# Auxillary_Supply_UCC28740.net
KiCad netlist of a schematic drawn in Altium Designer
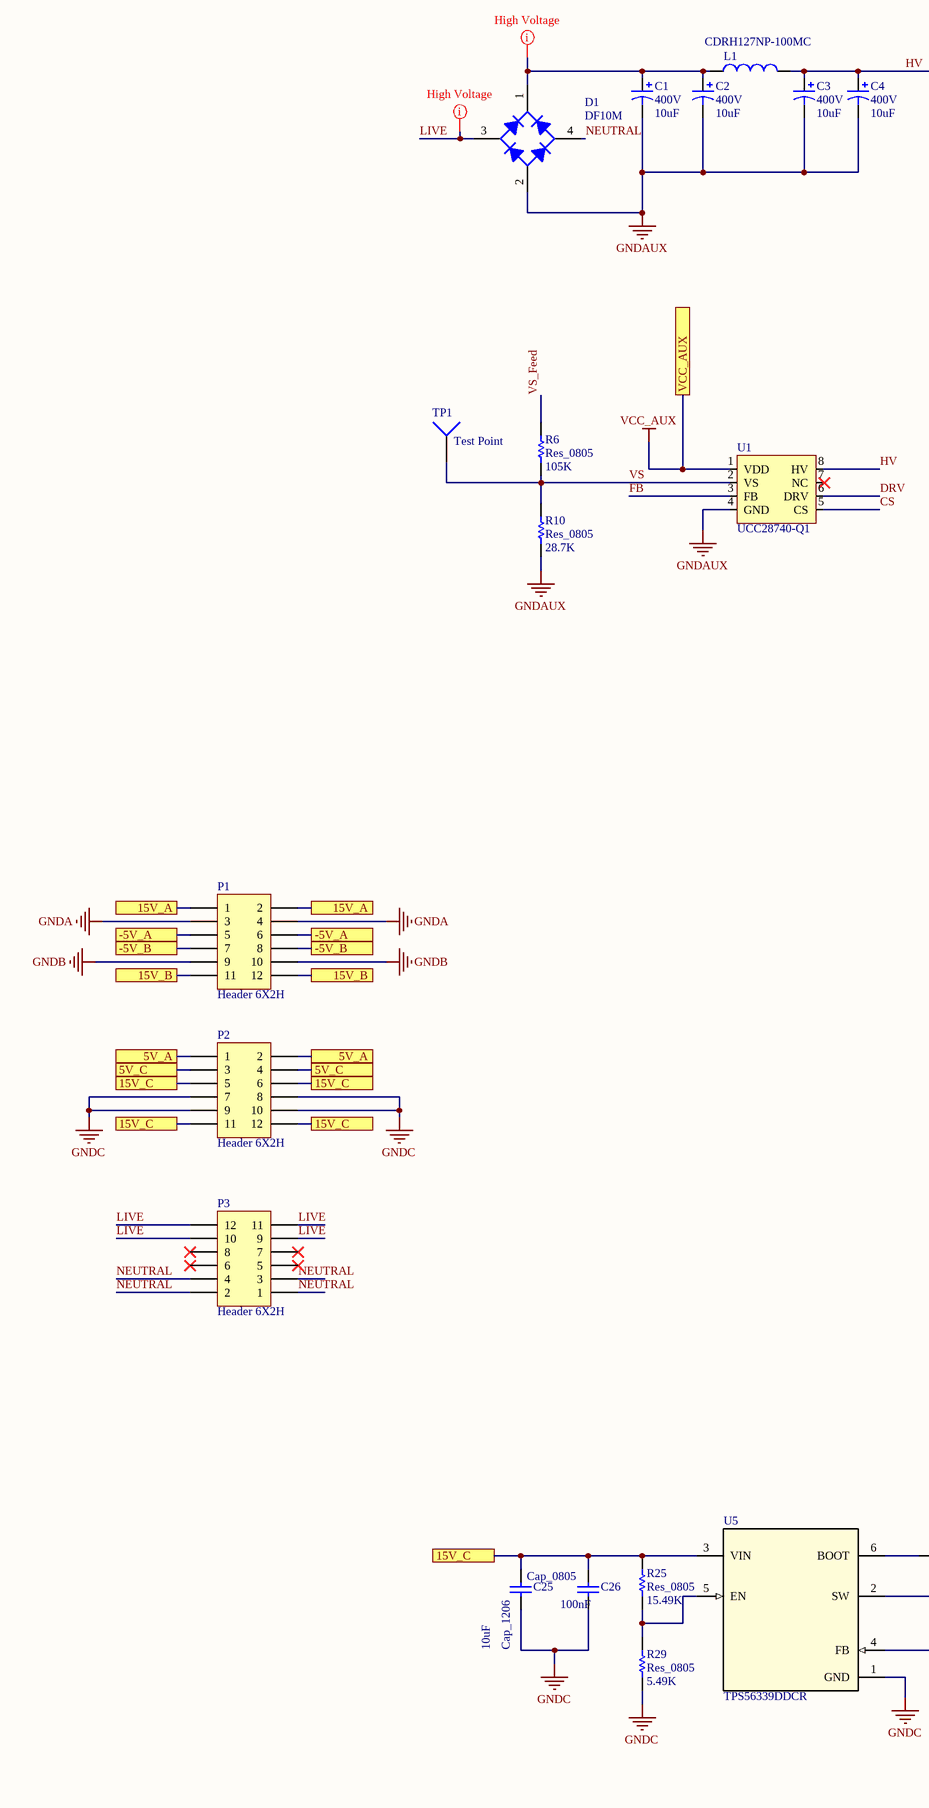
[diagram p0: Auxillary_Supply_UCC28740.SchDoc, left]
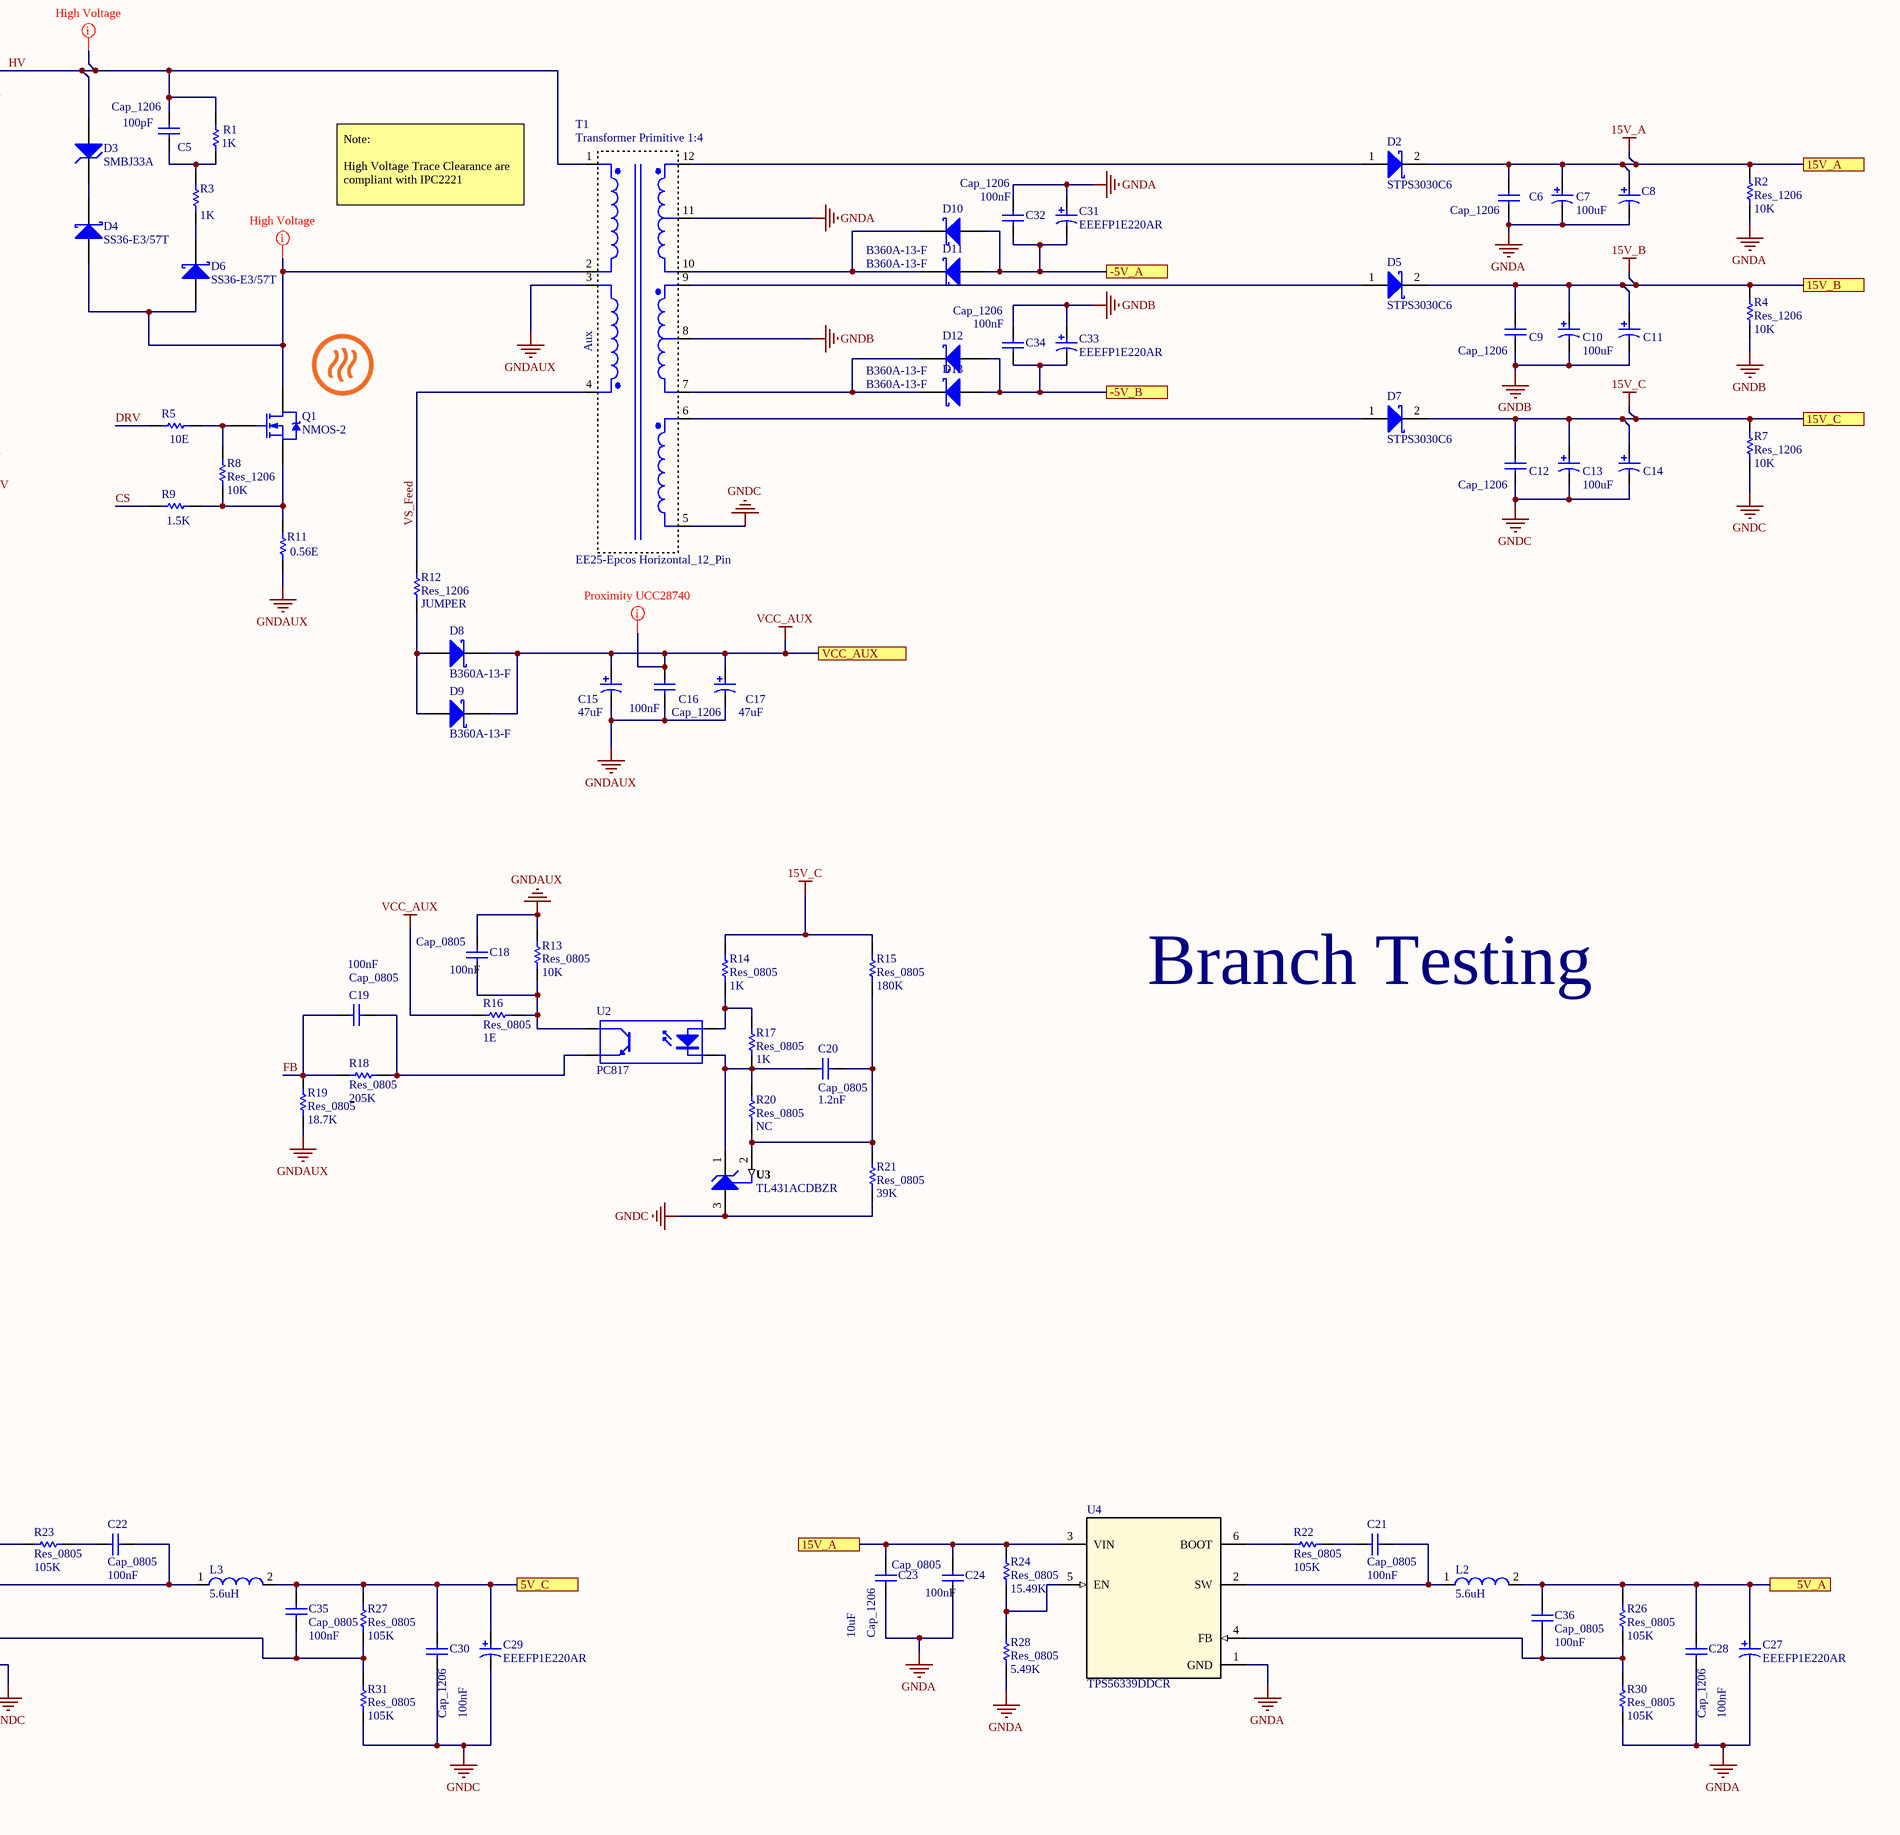
[diagram p1: Auxillary_Supply_UCC28740.SchDoc, right]

(export (version "E")
  (design (tool "Eeschema 10.0.6"))
  (components
    (comp (ref "C1")
      (value "400V")
      (footprint "10uF_400V")
      (description "Polarized Capacitor (Radial)")
      (fields (field (name "ALTIUM_VALUE") "10uF") (field (name "PUBLISHER") "Altium Limited"))
      (libsource (lib "Miscellaneous Devices") (part "Cap Pol1"))
    )
    (comp (ref "C2")
      (value "400V")
      (footprint "10uF_400V")
      (description "Polarized Capacitor (Radial)")
      (fields (field (name "ALTIUM_VALUE") "10uF") (field (name "PUBLISHER") "Altium Limited"))
      (libsource (lib "Miscellaneous Devices") (part "Cap Pol1"))
    )
    (comp (ref "C3")
      (value "400V")
      (footprint "10uF_400V")
      (description "Polarized Capacitor (Radial)")
      (fields (field (name "ALTIUM_VALUE") "10uF") (field (name "PUBLISHER") "Altium Limited"))
      (libsource (lib "Miscellaneous Devices") (part "Cap Pol1"))
    )
    (comp (ref "C4")
      (value "400V")
      (footprint "10uF_400V")
      (description "Polarized Capacitor (Radial)")
      (fields (field (name "ALTIUM_VALUE") "10uF") (field (name "PUBLISHER") "Altium Limited"))
      (libsource (lib "Miscellaneous Devices") (part "Cap Pol1"))
    )
    (comp (ref "C5")
      (value "Cap_1206")
      (footprint "Chip_CAP_1206")
      (description "Capacitor")
      (fields (field (name "ALTIUM_VALUE") "100pF") (field (name "PUBLISHER") "Altium Limited"))
      (libsource (lib "Miscellaneous Devices") (part "Cap"))
    )
    (comp (ref "C6")
      (value "Cap_1206")
      (footprint "Chip_CAP_1206")
      (description "Capacitor")
      (fields (field (name "PUBLISHER") "Altium Limited"))
      (libsource (lib "Miscellaneous Devices") (part "Cap"))
    )
    (comp (ref "C7")
      (value "100uF")
      (footprint "PNSC-FK-V-F_V")
      (fields (field (name "MANUFACTURER") "Panasonic"))
      (libsource (lib "Altium Content Vault") (part "CAP-P-2"))
    )
    (comp (ref "C8")
      (value "100uF")
      (footprint "PNSC-FK-V-F_V")
      (fields (field (name "MANUFACTURER") "Panasonic"))
      (libsource (lib "Altium Content Vault") (part "CAP-P-2"))
    )
    (comp (ref "C9")
      (value "Cap_1206")
      (footprint "Chip_CAP_1206")
      (description "Capacitor")
      (fields (field (name "PUBLISHER") "Altium Limited"))
      (libsource (lib "Miscellaneous Devices") (part "Cap"))
    )
    (comp (ref "C10")
      (value "100uF")
      (footprint "PNSC-FK-V-F_V")
      (fields (field (name "MANUFACTURER") "Panasonic"))
      (libsource (lib "Altium Content Vault") (part "CAP-P-2"))
    )
    (comp (ref "C11")
      (value "100uF")
      (footprint "PNSC-FK-V-F_V")
      (fields (field (name "MANUFACTURER") "Panasonic"))
      (libsource (lib "Altium Content Vault") (part "CAP-P-2"))
    )
    (comp (ref "C12")
      (value "Cap_1206")
      (footprint "Chip_CAP_1206")
      (description "Capacitor")
      (fields (field (name "PUBLISHER") "Altium Limited"))
      (libsource (lib "Miscellaneous Devices") (part "Cap"))
    )
    (comp (ref "C13")
      (value "100uF")
      (footprint "PNSC-FK-V-F_V")
      (fields (field (name "MANUFACTURER") "Panasonic"))
      (libsource (lib "Altium Content Vault") (part "CAP-P-2"))
    )
    (comp (ref "C14")
      (value "100uF")
      (footprint "PNSC-FK-V-F_V")
      (fields (field (name "MANUFACTURER") "Panasonic"))
      (libsource (lib "Altium Content Vault") (part "CAP-P-2"))
    )
    (comp (ref "C15")
      (value "47uF")
      (footprint "PNSC-FP-V-D_V")
      (fields (field (name "MANUFACTURER") "Panasonic"))
      (libsource (lib "Altium Content Vault") (part "CAP-P-2"))
    )
    (comp (ref "C16")
      (value "Cap_1206")
      (footprint "Chip_CAP_1206")
      (description "Capacitor")
      (fields (field (name "ALTIUM_VALUE") "100nF") (field (name "PUBLISHER") "Altium Limited"))
      (libsource (lib "Miscellaneous Devices") (part "Cap"))
    )
    (comp (ref "C17")
      (value "47uF")
      (footprint "PNSC-FP-V-D_V")
      (fields (field (name "MANUFACTURER") "Panasonic"))
      (libsource (lib "Altium Content Vault") (part "CAP-P-2"))
    )
    (comp (ref "C18")
      (value "Cap_0805")
      (footprint "Chip_CAP_0805")
      (description "Capacitor")
      (fields (field (name "SIZE") "100nF") (field (name "PUBLISHER") "Altium Limited"))
      (libsource (lib "Miscellaneous Devices") (part "Cap"))
    )
    (comp (ref "C19")
      (value "Cap_0805")
      (footprint "Chip_CAP_0805")
      (description "Capacitor")
      (fields (field (name "SIZE") "100nF") (field (name "PUBLISHER") "Altium Limited"))
      (libsource (lib "Miscellaneous Devices") (part "Cap"))
    )
    (comp (ref "C20")
      (value "Cap_0805")
      (footprint "Chip_CAP_0805")
      (description "Capacitor")
      (fields (field (name "SIZE") "1.2nF") (field (name "PUBLISHER") "Altium Limited"))
      (libsource (lib "Miscellaneous Devices") (part "Cap"))
    )
    (comp (ref "C21")
      (value "Cap_0805")
      (footprint "Chip_CAP_0805")
      (description "Capacitor")
      (fields (field (name "SIZE") "100nF") (field (name "PUBLISHER") "Altium Limited"))
      (libsource (lib "Miscellaneous Devices") (part "Cap"))
    )
    (comp (ref "C22")
      (value "Cap_0805")
      (footprint "Chip_CAP_0805")
      (description "Capacitor")
      (fields (field (name "SIZE") "100nF") (field (name "PUBLISHER") "Altium Limited"))
      (libsource (lib "Miscellaneous Devices") (part "Cap"))
    )
    (comp (ref "C23")
      (value "Cap_1206")
      (footprint "Chip_CAP_1206")
      (description "Capacitor")
      (fields (field (name "ALTIUM_VALUE") "10uF") (field (name "PUBLISHER") "Altium Limited"))
      (libsource (lib "Miscellaneous Devices") (part "Cap"))
    )
    (comp (ref "C24")
      (value "Cap_0805")
      (footprint "Chip_CAP_0805")
      (description "Capacitor")
      (fields (field (name "SIZE") "100nF") (field (name "PUBLISHER") "Altium Limited"))
      (libsource (lib "Miscellaneous Devices") (part "Cap"))
    )
    (comp (ref "C25")
      (value "Cap_1206")
      (footprint "Chip_CAP_1206")
      (description "Capacitor")
      (fields (field (name "ALTIUM_VALUE") "10uF") (field (name "PUBLISHER") "Altium Limited"))
      (libsource (lib "Miscellaneous Devices") (part "Cap"))
    )
    (comp (ref "C26")
      (value "Cap_0805")
      (footprint "Chip_CAP_0805")
      (description "Capacitor")
      (fields (field (name "SIZE") "100nF") (field (name "PUBLISHER") "Altium Limited"))
      (libsource (lib "Miscellaneous Devices") (part "Cap"))
    )
    (comp (ref "C27")
      (value "EEEFP1E220AR")
      (footprint "PNSC-FP-V-C_V")
      (fields (field (name "MANUFACTURER") "Panasonic"))
      (libsource (lib "Altium Content Vault") (part "CAP-P-2"))
    )
    (comp (ref "C28")
      (value "Cap_1206")
      (footprint "Chip_CAP_1206")
      (description "Capacitor")
      (fields (field (name "ALTIUM_VALUE") "100nF") (field (name "PUBLISHER") "Altium Limited"))
      (libsource (lib "Miscellaneous Devices") (part "Cap"))
    )
    (comp (ref "C29")
      (value "EEEFP1E220AR")
      (footprint "PNSC-FP-V-C_V")
      (fields (field (name "MANUFACTURER") "Panasonic"))
      (libsource (lib "Altium Content Vault") (part "CAP-P-2"))
    )
    (comp (ref "C30")
      (value "Cap_1206")
      (footprint "Chip_CAP_1206")
      (description "Capacitor")
      (fields (field (name "ALTIUM_VALUE") "100nF") (field (name "PUBLISHER") "Altium Limited"))
      (libsource (lib "Miscellaneous Devices") (part "Cap"))
    )
    (comp (ref "C31")
      (value "EEEFP1E220AR")
      (footprint "PNSC-FP-V-C_V")
      (fields (field (name "MANUFACTURER") "Panasonic"))
      (libsource (lib "Altium Content Vault") (part "CAP-P-2"))
    )
    (comp (ref "C32")
      (value "Cap_1206")
      (footprint "Chip_CAP_1206")
      (description "Capacitor")
      (fields (field (name "ALTIUM_VALUE") "100nF") (field (name "PUBLISHER") "Altium Limited"))
      (libsource (lib "Miscellaneous Devices") (part "Cap"))
    )
    (comp (ref "C33")
      (value "EEEFP1E220AR")
      (footprint "PNSC-FP-V-C_V")
      (fields (field (name "MANUFACTURER") "Panasonic"))
      (libsource (lib "Altium Content Vault") (part "CAP-P-2"))
    )
    (comp (ref "C34")
      (value "Cap_1206")
      (footprint "Chip_CAP_1206")
      (description "Capacitor")
      (fields (field (name "ALTIUM_VALUE") "100nF") (field (name "PUBLISHER") "Altium Limited"))
      (libsource (lib "Miscellaneous Devices") (part "Cap"))
    )
    (comp (ref "C35")
      (value "Cap_0805")
      (footprint "Chip_CAP_0805")
      (description "Capacitor")
      (fields (field (name "SIZE") "100nF") (field (name "PUBLISHER") "Altium Limited"))
      (libsource (lib "Miscellaneous Devices") (part "Cap"))
    )
    (comp (ref "C36")
      (value "Cap_0805")
      (footprint "Chip_CAP_0805")
      (description "Capacitor")
      (fields (field (name "SIZE") "100nF") (field (name "PUBLISHER") "Altium Limited"))
      (libsource (lib "Miscellaneous Devices") (part "Cap"))
    )
    (comp (ref "D1")
      (value "DF10M")
      (footprint "DF10M")
      (libsource (lib "Auxillary_Supply_UCC28740") (part "DF10M"))
    )
    (comp (ref "D2")
      (value "STPS3030C6")
      (footprint "DPAK254P1542X450-4N")
      (description "Schottky Rectifier")
      (fields (field (name "PUBLISHER") "Altium Limited"))
      (libsource (lib "IR Rectifier - Schottky") (part "11DQ06"))
    )
    (comp (ref "D3")
      (value "SMBJ33A")
      (footprint "FAIR-DO-214AA-2_V")
      (description "Transient Voltage Suppressor, 600 W, 33 V, -55 to 150 degC, 2-Pin SMD, RoHS, Tape and Reel")
      (fields (field (name "MANUFACTURER") "FairchildSemiconductor"))
      (libsource (lib "Altium Content Vault") (part "DZEN-AK-2"))
    )
    (comp (ref "D4")
      (value "SS36-E3/57T")
      (footprint "VISH-DO-214AB-2_V")
      (fields (field (name "MANUFACTURER") "Vishay"))
      (libsource (lib "Altium Content Vault") (part "DSKY-AK-2"))
    )
    (comp (ref "D5")
      (value "STPS3030C6")
      (footprint "DPAK254P1542X450-4N")
      (description "Schottky Rectifier")
      (fields (field (name "PUBLISHER") "Altium Limited"))
      (libsource (lib "IR Rectifier - Schottky") (part "11DQ06"))
    )
    (comp (ref "D6")
      (value "SS36-E3/57T")
      (footprint "VISH-DO-214AB-2_V")
      (fields (field (name "MANUFACTURER") "Vishay"))
      (libsource (lib "Altium Content Vault") (part "DSKY-AK-2"))
    )
    (comp (ref "D7")
      (value "STPS3030C6")
      (footprint "DPAK254P1542X450-4N")
      (description "Schottky Rectifier")
      (fields (field (name "PUBLISHER") "Altium Limited"))
      (libsource (lib "IR Rectifier - Schottky") (part "11DQ06"))
    )
    (comp (ref "D8")
      (value "B360A-13-F")
      (footprint "DIOD-B360A_V")
      (description "Schottky Barrier Rectifier, 3 A, -55 to 150 degC, 2-Pin Molded, RoHS, Tape and Reel")
      (fields (field (name "MANUFACTURER") "DiodesIncorporated"))
      (libsource (lib "Altium Content Vault") (part "DSKY-AK-2"))
    )
    (comp (ref "D9")
      (value "B360A-13-F")
      (footprint "DIOD-B360A_V")
      (description "Schottky Barrier Rectifier, 3 A, -55 to 150 degC, 2-Pin Molded, RoHS, Tape and Reel")
      (fields (field (name "MANUFACTURER") "DiodesIncorporated"))
      (libsource (lib "Altium Content Vault") (part "DSKY-AK-2"))
    )
    (comp (ref "D10")
      (value "B360A-13-F")
      (footprint "DIOD-B360A_V")
      (description "Schottky Barrier Rectifier, 3 A, -55 to 150 degC, 2-Pin Molded, RoHS, Tape and Reel")
      (fields (field (name "MANUFACTURER") "DiodesIncorporated"))
      (libsource (lib "Altium Content Vault") (part "DSKY-AK-2"))
    )
    (comp (ref "D11")
      (value "B360A-13-F")
      (footprint "DIOD-B360A_V")
      (description "Schottky Barrier Rectifier, 3 A, -55 to 150 degC, 2-Pin Molded, RoHS, Tape and Reel")
      (fields (field (name "MANUFACTURER") "DiodesIncorporated"))
      (libsource (lib "Altium Content Vault") (part "DSKY-AK-2"))
    )
    (comp (ref "D12")
      (value "B360A-13-F")
      (footprint "DIOD-B360A_V")
      (description "Schottky Barrier Rectifier, 3 A, -55 to 150 degC, 2-Pin Molded, RoHS, Tape and Reel")
      (fields (field (name "MANUFACTURER") "DiodesIncorporated"))
      (libsource (lib "Altium Content Vault") (part "DSKY-AK-2"))
    )
    (comp (ref "D13")
      (value "B360A-13-F")
      (footprint "DIOD-B360A_V")
      (description "Schottky Barrier Rectifier, 3 A, -55 to 150 degC, 2-Pin Molded, RoHS, Tape and Reel")
      (fields (field (name "MANUFACTURER") "DiodesIncorporated"))
      (libsource (lib "Altium Content Vault") (part "DSKY-AK-2"))
    )
    (comp (ref "L1")
      (value "CDRH127NP-100MC")
      (footprint "SUMI-CDRH127_V")
      (description "Power Inductor, 10 uH, +/- 20%, -40 to 100 degC, 2-Pin SMD, RoHS, Tape and Reel")
      (fields (field (name "MANUFACTURER") "Sumida") (field (name "TOLERANCE") "±20%"))
      (libsource (lib "Altium Content Vault") (part "IND-2"))
    )
    (comp (ref "L2")
      (value "5.6uH")
      (footprint "WE-PD-L")
      (description "SMD-Shielded Power Inductor WE-PD, L = 4.70 µH")
      (libsource (lib "Altium Content Vault") (part "PAS-IND-INDUCTOR-2"))
    )
    (comp (ref "L3")
      (value "5.6uH")
      (footprint "WE-PD-L")
      (description "SMD-Shielded Power Inductor WE-PD, L = 4.70 µH")
      (libsource (lib "Altium Content Vault") (part "PAS-IND-INDUCTOR-2"))
    )
    (comp (ref "P1")
      (value "Header 6X2H")
      (footprint "Header_6X2")
      (description "Header, 6-Pin, Dual row, Right Angle")
      (fields (field (name "PUBLISHER") "Altium Limited"))
      (libsource (lib "") (part "Header 6X2H_1"))
    )
    (comp (ref "P2")
      (value "Header 6X2H")
      (footprint "Header_6X2")
      (description "Header, 6-Pin, Dual row, Right Angle")
      (fields (field (name "PUBLISHER") "Altium Limited"))
      (libsource (lib "") (part "Header 6X2H_1"))
    )
    (comp (ref "P3")
      (value "Header 6X2H")
      (footprint "Header_6X2")
      (description "Header, 6-Pin, Dual row, Right Angle")
      (fields (field (name "PUBLISHER") "Altium Limited"))
      (libsource (lib "Miscellaneous Connectors") (part "Header 6X2H"))
    )
    (comp (ref "Q1")
      (value "NMOS-2")
      (footprint "DPAK254P1542X450-3N - Thermal")
      (description "N-Channel Power MOSFET")
      (fields (field (name "PUBLISHER") "Altium Limited"))
      (libsource (lib "Miscellaneous Devices") (part "NMOS-2"))
    )
    (comp (ref "R1")
      (value "1K")
      (footprint "Chip_Res_1206")
      (description "Resistor")
      (fields (field (name "Comment") "Res_1206") (field (name "PUBLISHER") "Altium Limited"))
      (libsource (lib "Miscellaneous Devices") (part "Res1"))
    )
    (comp (ref "R2")
      (value "Res_1206")
      (footprint "Chip_Res_1206")
      (description "Resistor")
      (fields (field (name "ALTIUM_VALUE") "10K") (field (name "PUBLISHER") "Altium Limited"))
      (libsource (lib "Miscellaneous Devices") (part "Res1"))
    )
    (comp (ref "R3")
      (value "1K")
      (footprint "Chip_Res_1206")
      (description "Resistor")
      (fields (field (name "Comment") "Res_1206") (field (name "PUBLISHER") "Altium Limited"))
      (libsource (lib "Miscellaneous Devices") (part "Res1"))
    )
    (comp (ref "R4")
      (value "Res_1206")
      (footprint "Chip_Res_1206")
      (description "Resistor")
      (fields (field (name "ALTIUM_VALUE") "10K") (field (name "PUBLISHER") "Altium Limited"))
      (libsource (lib "Miscellaneous Devices") (part "Res1"))
    )
    (comp (ref "R5")
      (value "10E")
      (footprint "Chip_Res_1206")
      (description "Resistor")
      (fields (field (name "Comment") "Res_1206") (field (name "PUBLISHER") "Altium Limited"))
      (libsource (lib "Miscellaneous Devices") (part "Res1"))
    )
    (comp (ref "R6")
      (value "Res_0805")
      (footprint "Chip_Res_0805")
      (description "Resistor")
      (fields (field (name "ALTIUM_VALUE") "105K") (field (name "PUBLISHER") "Altium Limited"))
      (libsource (lib "Miscellaneous Devices") (part "Res1"))
    )
    (comp (ref "R7")
      (value "Res_1206")
      (footprint "Chip_Res_1206")
      (description "Resistor")
      (fields (field (name "ALTIUM_VALUE") "10K") (field (name "PUBLISHER") "Altium Limited"))
      (libsource (lib "Miscellaneous Devices") (part "Res1"))
    )
    (comp (ref "R8")
      (value "Res_1206")
      (footprint "Chip_Res_1206")
      (description "Resistor")
      (fields (field (name "ALTIUM_VALUE") "10K") (field (name "PUBLISHER") "Altium Limited"))
      (libsource (lib "Miscellaneous Devices") (part "Res1"))
    )
    (comp (ref "R9")
      (value "1.5K")
      (footprint "Chip_Res_1206")
      (description "Resistor")
      (fields (field (name "Comment") "Res_1206") (field (name "PUBLISHER") "Altium Limited"))
      (libsource (lib "Miscellaneous Devices") (part "Res1"))
    )
    (comp (ref "R10")
      (value "Res_0805")
      (footprint "Chip_Res_0805")
      (description "Resistor")
      (fields (field (name "ALTIUM_VALUE") "28.7K") (field (name "PUBLISHER") "Altium Limited"))
      (libsource (lib "Miscellaneous Devices") (part "Res1"))
    )
    (comp (ref "R11")
      (value "0.56E")
      (footprint "Chip2PinSM127P600-8N_2512")
      (description "Resistor")
      (fields (field (name "Comment") "Res_2512") (field (name "PUBLISHER") "Altium Limited"))
      (libsource (lib "Miscellaneous Devices") (part "Res1"))
    )
    (comp (ref "R12")
      (value "Res_1206")
      (footprint "Chip_Res_1206")
      (description "Resistor")
      (fields (field (name "ALTIUM_VALUE") "JUMPER") (field (name "PUBLISHER") "Altium Limited"))
      (libsource (lib "Miscellaneous Devices") (part "Res1"))
    )
    (comp (ref "R13")
      (value "Res_0805")
      (footprint "Chip_Res_0805")
      (description "Resistor")
      (fields (field (name "ALTIUM_VALUE") "10K") (field (name "PUBLISHER") "Altium Limited"))
      (libsource (lib "Miscellaneous Devices") (part "Res1"))
    )
    (comp (ref "R14")
      (value "Res_0805")
      (footprint "Chip_Res_0805")
      (description "Resistor")
      (fields (field (name "ALTIUM_VALUE") "1K") (field (name "PUBLISHER") "Altium Limited"))
      (libsource (lib "Miscellaneous Devices") (part "Res1"))
    )
    (comp (ref "R15")
      (value "Res_0805")
      (footprint "Chip_Res_0805")
      (description "Resistor")
      (fields (field (name "ALTIUM_VALUE") "180K") (field (name "PUBLISHER") "Altium Limited"))
      (libsource (lib "Miscellaneous Devices") (part "Res1"))
    )
    (comp (ref "R16")
      (value "Res_0805")
      (footprint "Chip_Res_0805")
      (description "Resistor")
      (fields (field (name "ALTIUM_VALUE") "1E") (field (name "PUBLISHER") "Altium Limited"))
      (libsource (lib "Miscellaneous Devices") (part "Res1"))
    )
    (comp (ref "R17")
      (value "Res_0805")
      (footprint "Chip_Res_0805")
      (description "Resistor")
      (fields (field (name "ALTIUM_VALUE") "1K") (field (name "PUBLISHER") "Altium Limited"))
      (libsource (lib "Miscellaneous Devices") (part "Res1"))
    )
    (comp (ref "R18")
      (value "Res_0805")
      (footprint "Chip_Res_0805")
      (description "Resistor")
      (fields (field (name "ALTIUM_VALUE") "205K") (field (name "PUBLISHER") "Altium Limited"))
      (libsource (lib "Miscellaneous Devices") (part "Res1"))
    )
    (comp (ref "R19")
      (value "Res_0805")
      (footprint "Chip_Res_0805")
      (description "Resistor")
      (fields (field (name "ALTIUM_VALUE") "18.7K") (field (name "PUBLISHER") "Altium Limited"))
      (libsource (lib "Miscellaneous Devices") (part "Res1"))
    )
    (comp (ref "R20")
      (value "Res_0805")
      (footprint "Chip_Res_0805")
      (description "Resistor")
      (fields (field (name "ALTIUM_VALUE") "NC") (field (name "PUBLISHER") "Altium Limited"))
      (libsource (lib "Miscellaneous Devices") (part "Res1"))
    )
    (comp (ref "R21")
      (value "Res_0805")
      (footprint "Chip_Res_0805")
      (description "Resistor")
      (fields (field (name "ALTIUM_VALUE") "39K") (field (name "PUBLISHER") "Altium Limited"))
      (libsource (lib "Miscellaneous Devices") (part "Res1"))
    )
    (comp (ref "R22")
      (value "Res_0805")
      (footprint "Chip_Res_0805")
      (description "Resistor")
      (fields (field (name "ALTIUM_VALUE") "105K") (field (name "PUBLISHER") "Altium Limited"))
      (libsource (lib "Miscellaneous Devices") (part "Res1"))
    )
    (comp (ref "R23")
      (value "Res_0805")
      (footprint "Chip_Res_0805")
      (description "Resistor")
      (fields (field (name "ALTIUM_VALUE") "105K") (field (name "PUBLISHER") "Altium Limited"))
      (libsource (lib "Miscellaneous Devices") (part "Res1"))
    )
    (comp (ref "R24")
      (value "Res_0805")
      (footprint "Chip_Res_0805")
      (description "Resistor")
      (fields (field (name "ALTIUM_VALUE") "15.49K") (field (name "PUBLISHER") "Altium Limited"))
      (libsource (lib "Miscellaneous Devices") (part "Res1"))
    )
    (comp (ref "R25")
      (value "Res_0805")
      (footprint "Chip_Res_0805")
      (description "Resistor")
      (fields (field (name "ALTIUM_VALUE") "15.49K") (field (name "PUBLISHER") "Altium Limited"))
      (libsource (lib "Miscellaneous Devices") (part "Res1"))
    )
    (comp (ref "R26")
      (value "Res_0805")
      (footprint "Chip_Res_0805")
      (description "Resistor")
      (fields (field (name "ALTIUM_VALUE") "105K") (field (name "PUBLISHER") "Altium Limited"))
      (libsource (lib "Miscellaneous Devices") (part "Res1"))
    )
    (comp (ref "R27")
      (value "Res_0805")
      (footprint "Chip_Res_0805")
      (description "Resistor")
      (fields (field (name "ALTIUM_VALUE") "105K") (field (name "PUBLISHER") "Altium Limited"))
      (libsource (lib "Miscellaneous Devices") (part "Res1"))
    )
    (comp (ref "R28")
      (value "Res_0805")
      (footprint "Chip_Res_0805")
      (description "Resistor")
      (fields (field (name "ALTIUM_VALUE") "5.49K") (field (name "PUBLISHER") "Altium Limited"))
      (libsource (lib "Miscellaneous Devices") (part "Res1"))
    )
    (comp (ref "R29")
      (value "Res_0805")
      (footprint "Chip_Res_0805")
      (description "Resistor")
      (fields (field (name "ALTIUM_VALUE") "5.49K") (field (name "PUBLISHER") "Altium Limited"))
      (libsource (lib "Miscellaneous Devices") (part "Res1"))
    )
    (comp (ref "R30")
      (value "Res_0805")
      (footprint "Chip_Res_0805")
      (description "Resistor")
      (fields (field (name "ALTIUM_VALUE") "105K") (field (name "PUBLISHER") "Altium Limited"))
      (libsource (lib "Miscellaneous Devices") (part "Res1"))
    )
    (comp (ref "R31")
      (value "Res_0805")
      (footprint "Chip_Res_0805")
      (description "Resistor")
      (fields (field (name "ALTIUM_VALUE") "105K") (field (name "PUBLISHER") "Altium Limited"))
      (libsource (lib "Miscellaneous Devices") (part "Res1"))
    )
    (comp (ref "T1")
      (value "EE25-Epcos Horizontal_12_Pin")
      (footprint "PQ26_20")
      (libsource (lib "Auxillary_Supply_UCC28740") (part "EE25-Epcos Horizontal_12_Pin"))
    )
    (comp (ref "TP1")
      (value "Test Point")
      (footprint "PIN1")
      (fields (field (name "PUBLISHER") "Altium Limited"))
      (libsource (lib "Miscellaneous Connectors") (part "Socket"))
    )
    (comp (ref "U1")
      (value "UCC28740-Q1")
      (footprint "SOIC127P570X175_HS-9N")
      (libsource (lib "Auxillary_Supply_UCC28740") (part "UCC28740-Q1"))
    )
    (comp (ref "U2")
      (value "PC817")
      (footprint "LTV-817")
      (description "4-Pin Phototransistor Optocoupler")
      (fields (field (name "PUBLISHER") "Altium Limited"))
      (libsource (lib "Miscellaneous Devices") (part "Optoisolator1"))
    )
    (comp (ref "U3")
      (value "TL431ACDBZR")
      (footprint "DBZ0003A_L")
      (fields (field (name "MANUFACTURER") "Texas Instruments"))
      (libsource (lib "Altium Content Vault") (part "TI-TL431ADBZ3"))
    )
    (comp (ref "U4")
      (value "TPS56339DDCR")
      (footprint "SOT95P278X110-6N")
      (description "Imported")
      (fields (field (name "MANUFACTURER") "Texas Instruments"))
      (libsource (lib "Auxillary_Supply_UCC28740") (part "TPS56339DDCR"))
    )
    (comp (ref "U5")
      (value "TPS56339DDCR")
      (footprint "SOT95P278X110-6N")
      (description "Imported")
      (fields (field (name "MANUFACTURER") "Texas Instruments"))
      (libsource (lib "Auxillary_Supply_UCC28740") (part "TPS56339DDCR"))
    )
  )
  (nets
    (net (code "1") (name "/-5V_A") (class "Default")
      (node (ref "C31") (pin "2") (pinfunction "2_2") (pintype "passive"))
      (node (ref "C32") (pin "2") (pinfunction "2_2") (pintype "passive"))
      (node (ref "D10") (pin "1") (pinfunction "A_1") (pintype "passive"))
      (node (ref "D11") (pin "1") (pinfunction "A_1") (pintype "passive"))
      (node (ref "P1") (pin "5") (pinfunction "5_5") (pintype "passive"))
      (node (ref "P1") (pin "6") (pinfunction "6_6") (pintype "passive"))
    )
    (net (code "2") (name "/-5V_B") (class "Default")
      (node (ref "C33") (pin "2") (pinfunction "2_2") (pintype "passive"))
      (node (ref "C34") (pin "2") (pinfunction "2_2") (pintype "passive"))
      (node (ref "D12") (pin "1") (pinfunction "A_1") (pintype "passive"))
      (node (ref "D13") (pin "1") (pinfunction "A_1") (pintype "passive"))
      (node (ref "P1") (pin "7") (pinfunction "7_7") (pintype "passive"))
      (node (ref "P1") (pin "8") (pinfunction "8_8") (pintype "passive"))
    )
    (net (code "3") (name "/5V_A") (class "Default")
      (node (ref "C27") (pin "1") (pinfunction "1_1") (pintype "passive"))
      (node (ref "C28") (pin "1") (pinfunction "1_1") (pintype "passive"))
      (node (ref "C36") (pin "2") (pinfunction "2_2") (pintype "passive"))
      (node (ref "L2") (pin "2") (pinfunction "2_2") (pintype "passive"))
      (node (ref "P2") (pin "1") (pinfunction "1_1") (pintype "passive"))
      (node (ref "P2") (pin "2") (pinfunction "2_2") (pintype "passive"))
      (node (ref "R26") (pin "2") (pinfunction "2_2") (pintype "passive"))
    )
    (net (code "4") (name "/5V_C") (class "Default")
      (node (ref "C29") (pin "1") (pinfunction "1_1") (pintype "passive"))
      (node (ref "C30") (pin "1") (pinfunction "1_1") (pintype "passive"))
      (node (ref "C35") (pin "2") (pinfunction "2_2") (pintype "passive"))
      (node (ref "L3") (pin "2") (pinfunction "2_2") (pintype "passive"))
      (node (ref "P2") (pin "3") (pinfunction "3_3") (pintype "passive"))
      (node (ref "P2") (pin "4") (pinfunction "4_4") (pintype "passive"))
      (node (ref "R27") (pin "2") (pinfunction "2_2") (pintype "passive"))
    )
    (net (code "6") (name "/CS") (class "Default")
      (node (ref "R9") (pin "1") (pinfunction "1_1") (pintype "passive"))
      (node (ref "U1") (pin "5") (pinfunction "CS_5") (pintype "passive"))
    )
    (net (code "7") (name "/DRV") (class "Default")
      (node (ref "R5") (pin "1") (pinfunction "1_1") (pintype "passive"))
      (node (ref "U1") (pin "6") (pinfunction "DRV_6") (pintype "passive"))
    )
    (net (code "8") (name "/FB") (class "Default")
      (node (ref "C19") (pin "2") (pinfunction "2_2") (pintype "passive"))
      (node (ref "R18") (pin "1") (pinfunction "1_1") (pintype "passive"))
      (node (ref "R19") (pin "2") (pinfunction "2_2") (pintype "passive"))
      (node (ref "U1") (pin "3") (pinfunction "FB_3") (pintype "passive"))
    )
    (net (code "9") (name "/HV") (class "Default")
      (node (ref "C3") (pin "1") (pinfunction "1_1") (pintype "passive"))
      (node (ref "C4") (pin "1") (pinfunction "1_1") (pintype "passive"))
      (node (ref "C5") (pin "2") (pinfunction "2_2") (pintype "passive"))
      (node (ref "D3") (pin "1") (pinfunction "A_1") (pintype "passive"))
      (node (ref "L1") (pin "2") (pinfunction "2_2") (pintype "passive"))
      (node (ref "R1") (pin "2") (pinfunction "2_2") (pintype "passive"))
      (node (ref "T1") (pin "1") (pinfunction "1_1") (pintype "passive"))
      (node (ref "U1") (pin "8") (pinfunction "HV_8") (pintype "passive"))
    )
    (net (code "10") (name "/LIVE") (class "Default")
      (node (ref "D1") (pin "3") (pinfunction "C_3") (pintype "passive"))
      (node (ref "P3") (pin "10") (pinfunction "10_10") (pintype "passive"))
      (node (ref "P3") (pin "11") (pinfunction "11_11") (pintype "passive"))
      (node (ref "P3") (pin "12") (pinfunction "12_12") (pintype "passive"))
      (node (ref "P3") (pin "9") (pinfunction "9_9") (pintype "passive"))
    )
    (net (code "11") (name "/NEUTRAL") (class "Default")
      (node (ref "D1") (pin "4") (pinfunction "C_4") (pintype "passive"))
      (node (ref "P3") (pin "1") (pinfunction "1_1") (pintype "passive"))
      (node (ref "P3") (pin "2") (pinfunction "2_2") (pintype "passive"))
      (node (ref "P3") (pin "3") (pinfunction "3_3") (pintype "passive"))
      (node (ref "P3") (pin "4") (pinfunction "4_4") (pintype "passive"))
    )
    (net (code "12") (name "/VS") (class "Default")
      (node (ref "R10") (pin "2") (pinfunction "2_2") (pintype "passive"))
      (node (ref "R6") (pin "1") (pinfunction "1_1") (pintype "passive"))
      (node (ref "TP1") (pin "1") (pinfunction "1_1") (pintype "passive"))
      (node (ref "U1") (pin "2") (pinfunction "VS_2") (pintype "passive"))
    )
    (net (code "13") (name "/VS_Feed") (class "Default")
      (node (ref "R12") (pin "2") (pinfunction "2_2") (pintype "passive"))
      (node (ref "R6") (pin "2") (pinfunction "2_2") (pintype "passive"))
      (node (ref "T1") (pin "4") (pinfunction "4_4") (pintype "passive"))
    )
    (net (code "14") (name "15V_A") (class "Default")
      (node (ref "C23") (pin "1") (pinfunction "1_1") (pintype "passive"))
      (node (ref "C24") (pin "1") (pinfunction "1_1") (pintype "passive"))
      (node (ref "C6") (pin "2") (pinfunction "2_2") (pintype "passive"))
      (node (ref "C7") (pin "1") (pinfunction "1_1") (pintype "passive"))
      (node (ref "C8") (pin "1") (pinfunction "1_1") (pintype "passive"))
      (node (ref "D2") (pin "2") (pinfunction "K_2") (pintype "passive"))
      (node (ref "P1") (pin "1") (pinfunction "1_1") (pintype "passive"))
      (node (ref "P1") (pin "2") (pinfunction "2_2") (pintype "passive"))
      (node (ref "R2") (pin "2") (pinfunction "2_2") (pintype "passive"))
      (node (ref "R24") (pin "2") (pinfunction "2_2") (pintype "passive"))
      (node (ref "U4") (pin "3") (pinfunction "VIN_3") (pintype "power_in"))
    )
    (net (code "15") (name "15V_B") (class "Default")
      (node (ref "C10") (pin "1") (pinfunction "1_1") (pintype "passive"))
      (node (ref "C11") (pin "1") (pinfunction "1_1") (pintype "passive"))
      (node (ref "C9") (pin "2") (pinfunction "2_2") (pintype "passive"))
      (node (ref "D5") (pin "2") (pinfunction "K_2") (pintype "passive"))
      (node (ref "P1") (pin "11") (pinfunction "11_11") (pintype "passive"))
      (node (ref "P1") (pin "12") (pinfunction "12_12") (pintype "passive"))
      (node (ref "R4") (pin "2") (pinfunction "2_2") (pintype "passive"))
    )
    (net (code "16") (name "15V_C") (class "Default")
      (node (ref "C12") (pin "2") (pinfunction "2_2") (pintype "passive"))
      (node (ref "C13") (pin "1") (pinfunction "1_1") (pintype "passive"))
      (node (ref "C14") (pin "1") (pinfunction "1_1") (pintype "passive"))
      (node (ref "C25") (pin "1") (pinfunction "1_1") (pintype "passive"))
      (node (ref "C26") (pin "1") (pinfunction "1_1") (pintype "passive"))
      (node (ref "D7") (pin "2") (pinfunction "K_2") (pintype "passive"))
      (node (ref "P2") (pin "11") (pinfunction "11_11") (pintype "passive"))
      (node (ref "P2") (pin "12") (pinfunction "12_12") (pintype "passive"))
      (node (ref "P2") (pin "5") (pinfunction "5_5") (pintype "passive"))
      (node (ref "P2") (pin "6") (pinfunction "6_6") (pintype "passive"))
      (node (ref "R14") (pin "2") (pinfunction "2_2") (pintype "passive"))
      (node (ref "R15") (pin "1") (pinfunction "1_1") (pintype "passive"))
      (node (ref "R25") (pin "2") (pinfunction "2_2") (pintype "passive"))
      (node (ref "R7") (pin "2") (pinfunction "2_2") (pintype "passive"))
      (node (ref "U5") (pin "3") (pinfunction "VIN_3") (pintype "power_in"))
    )
    (net (code "17") (name "GNDA") (class "Default")
      (node (ref "C23") (pin "2") (pinfunction "2_2") (pintype "passive"))
      (node (ref "C24") (pin "2") (pinfunction "2_2") (pintype "passive"))
      (node (ref "C27") (pin "2") (pinfunction "2_2") (pintype "passive"))
      (node (ref "C28") (pin "2") (pinfunction "2_2") (pintype "passive"))
      (node (ref "C31") (pin "1") (pinfunction "1_1") (pintype "passive"))
      (node (ref "C32") (pin "1") (pinfunction "1_1") (pintype "passive"))
      (node (ref "C6") (pin "1") (pinfunction "1_1") (pintype "passive"))
      (node (ref "C7") (pin "2") (pinfunction "2_2") (pintype "passive"))
      (node (ref "C8") (pin "2") (pinfunction "2_2") (pintype "passive"))
      (node (ref "P1") (pin "3") (pinfunction "3_3") (pintype "passive"))
      (node (ref "P1") (pin "4") (pinfunction "4_4") (pintype "passive"))
      (node (ref "R2") (pin "1") (pinfunction "1_1") (pintype "passive"))
      (node (ref "R28") (pin "1") (pinfunction "1_1") (pintype "passive"))
      (node (ref "R30") (pin "1") (pinfunction "1_1") (pintype "passive"))
      (node (ref "T1") (pin "11") (pinfunction "11_11") (pintype "passive"))
      (node (ref "U4") (pin "1") (pinfunction "GND_1") (pintype "power_in"))
    )
    (net (code "18") (name "GNDAUX") (class "Default")
      (node (ref "C1") (pin "2") (pinfunction "2_2") (pintype "passive"))
      (node (ref "C15") (pin "2") (pinfunction "2_2") (pintype "passive"))
      (node (ref "C16") (pin "1") (pinfunction "1_1") (pintype "passive"))
      (node (ref "C17") (pin "2") (pinfunction "2_2") (pintype "passive"))
      (node (ref "C18") (pin "1") (pinfunction "1_1") (pintype "passive"))
      (node (ref "C2") (pin "2") (pinfunction "2_2") (pintype "passive"))
      (node (ref "C3") (pin "2") (pinfunction "2_2") (pintype "passive"))
      (node (ref "C4") (pin "2") (pinfunction "2_2") (pintype "passive"))
      (node (ref "D1") (pin "2") (pinfunction "A_2") (pintype "passive"))
      (node (ref "R10") (pin "1") (pinfunction "1_1") (pintype "passive"))
      (node (ref "R11") (pin "1") (pinfunction "1_1") (pintype "passive"))
      (node (ref "R13") (pin "2") (pinfunction "2_2") (pintype "passive"))
      (node (ref "R19") (pin "1") (pinfunction "1_1") (pintype "passive"))
      (node (ref "T1") (pin "3") (pinfunction "3_3") (pintype "passive"))
      (node (ref "U1") (pin "4") (pinfunction "GND_4") (pintype "power_in"))
    )
    (net (code "19") (name "GNDB") (class "Default")
      (node (ref "C10") (pin "2") (pinfunction "2_2") (pintype "passive"))
      (node (ref "C11") (pin "2") (pinfunction "2_2") (pintype "passive"))
      (node (ref "C33") (pin "1") (pinfunction "1_1") (pintype "passive"))
      (node (ref "C34") (pin "1") (pinfunction "1_1") (pintype "passive"))
      (node (ref "C9") (pin "1") (pinfunction "1_1") (pintype "passive"))
      (node (ref "P1") (pin "10") (pinfunction "10_10") (pintype "passive"))
      (node (ref "P1") (pin "9") (pinfunction "9_9") (pintype "passive"))
      (node (ref "R4") (pin "1") (pinfunction "1_1") (pintype "passive"))
      (node (ref "T1") (pin "8") (pinfunction "8_8") (pintype "passive"))
    )
    (net (code "20") (name "GNDC") (class "Default")
      (node (ref "C12") (pin "1") (pinfunction "1_1") (pintype "passive"))
      (node (ref "C13") (pin "2") (pinfunction "2_2") (pintype "passive"))
      (node (ref "C14") (pin "2") (pinfunction "2_2") (pintype "passive"))
      (node (ref "C25") (pin "2") (pinfunction "2_2") (pintype "passive"))
      (node (ref "C26") (pin "2") (pinfunction "2_2") (pintype "passive"))
      (node (ref "C29") (pin "2") (pinfunction "2_2") (pintype "passive"))
      (node (ref "C30") (pin "2") (pinfunction "2_2") (pintype "passive"))
      (node (ref "P2") (pin "10") (pinfunction "10_10") (pintype "passive"))
      (node (ref "P2") (pin "7") (pinfunction "7_7") (pintype "passive"))
      (node (ref "P2") (pin "8") (pinfunction "8_8") (pintype "passive"))
      (node (ref "P2") (pin "9") (pinfunction "9_9") (pintype "passive"))
      (node (ref "R21") (pin "1") (pinfunction "1_1") (pintype "passive"))
      (node (ref "R29") (pin "1") (pinfunction "1_1") (pintype "passive"))
      (node (ref "R31") (pin "1") (pinfunction "1_1") (pintype "passive"))
      (node (ref "R7") (pin "1") (pinfunction "1_1") (pintype "passive"))
      (node (ref "T1") (pin "5") (pinfunction "5_5") (pintype "passive"))
      (node (ref "U3") (pin "3") (pinfunction "ANODE_3") (pintype "passive"))
      (node (ref "U5") (pin "1") (pinfunction "GND_1") (pintype "power_in"))
    )
    (net (code "21") (name "Net-(C5-Pad1)") (class "Default")
      (node (ref "C5") (pin "1") (pinfunction "1_1") (pintype "passive"))
      (node (ref "R1") (pin "1") (pinfunction "1_1") (pintype "passive"))
      (node (ref "R3") (pin "2") (pinfunction "2_2") (pintype "passive"))
    )
    (net (code "22") (name "Net-(C21-Pad1)") (class "Default")
      (node (ref "C21") (pin "1") (pinfunction "1_1") (pintype "passive"))
      (node (ref "R22") (pin "1") (pinfunction "1_1") (pintype "passive"))
    )
    (net (code "23") (name "Net-(C22-Pad1)") (class "Default")
      (node (ref "C22") (pin "1") (pinfunction "1_1") (pintype "passive"))
      (node (ref "R23") (pin "1") (pinfunction "1_1") (pintype "passive"))
    )
    (net (code "24") (name "Net-(D1-K)") (class "Default")
      (node (ref "C1") (pin "1") (pinfunction "1_1") (pintype "passive"))
      (node (ref "C2") (pin "1") (pinfunction "1_1") (pintype "passive"))
      (node (ref "D1") (pin "1") (pinfunction "K_1") (pintype "passive"))
      (node (ref "L1") (pin "1") (pinfunction "1_1") (pintype "passive"))
    )
    (net (code "25") (name "Net-(D2-A)") (class "Default")
      (node (ref "D2") (pin "1") (pinfunction "A_1") (pintype "passive"))
      (node (ref "T1") (pin "12") (pinfunction "12_12") (pintype "passive"))
    )
    (net (code "26") (name "Net-(D3-K)") (class "Default")
      (node (ref "D3") (pin "2") (pinfunction "K_2") (pintype "passive"))
      (node (ref "D4") (pin "2") (pinfunction "K_2") (pintype "passive"))
    )
    (net (code "27") (name "Net-(D4-A)") (class "Default")
      (node (ref "D4") (pin "1") (pinfunction "A_1") (pintype "passive"))
      (node (ref "D6") (pin "1") (pinfunction "A_1") (pintype "passive"))
      (node (ref "Q1") (pin "2") (pinfunction "D_2") (pintype "passive"))
      (node (ref "T1") (pin "2") (pinfunction "1_2") (pintype "passive"))
    )
    (net (code "28") (name "Net-(D5-A)") (class "Default")
      (node (ref "D5") (pin "1") (pinfunction "A_1") (pintype "passive"))
      (node (ref "T1") (pin "9") (pinfunction "9_9") (pintype "passive"))
    )
    (net (code "29") (name "Net-(D6-K)") (class "Default")
      (node (ref "D6") (pin "2") (pinfunction "K_2") (pintype "passive"))
      (node (ref "R3") (pin "1") (pinfunction "1_1") (pintype "passive"))
    )
    (net (code "30") (name "Net-(D7-A)") (class "Default")
      (node (ref "D7") (pin "1") (pinfunction "A_1") (pintype "passive"))
      (node (ref "T1") (pin "6") (pinfunction "6_6") (pintype "passive"))
    )
    (net (code "31") (name "Net-(D8-A)") (class "Default")
      (node (ref "D8") (pin "1") (pinfunction "A_1") (pintype "passive"))
      (node (ref "D9") (pin "1") (pinfunction "A_1") (pintype "passive"))
      (node (ref "R12") (pin "1") (pinfunction "1_1") (pintype "passive"))
    )
    (net (code "32") (name "Net-(D10-K)") (class "Default")
      (node (ref "D10") (pin "2") (pinfunction "K_2") (pintype "passive"))
      (node (ref "D11") (pin "2") (pinfunction "K_2") (pintype "passive"))
      (node (ref "T1") (pin "10") (pinfunction "10_10") (pintype "passive"))
    )
    (net (code "33") (name "Net-(D12-K)") (class "Default")
      (node (ref "D12") (pin "2") (pinfunction "K_2") (pintype "passive"))
      (node (ref "D13") (pin "2") (pinfunction "K_2") (pintype "passive"))
      (node (ref "T1") (pin "7") (pinfunction "7_7") (pintype "passive"))
    )
    (net (code "34") (name "Net-(Q1-G)") (class "Default")
      (node (ref "Q1") (pin "1") (pinfunction "G_1") (pintype "passive"))
      (node (ref "R5") (pin "2") (pinfunction "2_2") (pintype "passive"))
      (node (ref "R8") (pin "2") (pinfunction "2_2") (pintype "passive"))
    )
    (net (code "35") (name "Net-(Q1-S)") (class "Default")
      (node (ref "Q1") (pin "3") (pinfunction "S_3") (pintype "passive"))
      (node (ref "R11") (pin "2") (pinfunction "2_2") (pintype "passive"))
      (node (ref "R8") (pin "1") (pinfunction "1_1") (pintype "passive"))
      (node (ref "R9") (pin "2") (pinfunction "2_2") (pintype "passive"))
    )
    (net (code "36") (name "Net-(U2-A)") (class "Default")
      (node (ref "R14") (pin "1") (pinfunction "1_1") (pintype "passive"))
      (node (ref "R17") (pin "2") (pinfunction "2_2") (pintype "passive"))
      (node (ref "U2") (pin "1") (pinfunction "A_1") (pintype "passive"))
    )
    (net (code "37") (name "Net-(U2-C)") (class "Default")
      (node (ref "C18") (pin "2") (pinfunction "2_2") (pintype "passive"))
      (node (ref "R13") (pin "1") (pinfunction "1_1") (pintype "passive"))
      (node (ref "R16") (pin "1") (pinfunction "1_1") (pintype "passive"))
      (node (ref "U2") (pin "4") (pinfunction "C_4") (pintype "passive"))
    )
    (net (code "38") (name "Net-(U2-E)") (class "Default")
      (node (ref "C19") (pin "1") (pinfunction "1_1") (pintype "passive"))
      (node (ref "R18") (pin "2") (pinfunction "2_2") (pintype "passive"))
      (node (ref "U2") (pin "3") (pinfunction "E_3") (pintype "passive"))
    )
    (net (code "39") (name "Net-(U2-K)") (class "Default")
      (node (ref "C20") (pin "1") (pinfunction "1_1") (pintype "passive"))
      (node (ref "R17") (pin "1") (pinfunction "1_1") (pintype "passive"))
      (node (ref "R20") (pin "2") (pinfunction "2_2") (pintype "passive"))
      (node (ref "U2") (pin "2") (pinfunction "K_2") (pintype "passive"))
      (node (ref "U3") (pin "1") (pinfunction "CATHODE_1") (pintype "passive"))
    )
    (net (code "40") (name "Net-(U3-REF)") (class "Default")
      (node (ref "C20") (pin "2") (pinfunction "2_2") (pintype "passive"))
      (node (ref "R15") (pin "2") (pinfunction "2_2") (pintype "passive"))
      (node (ref "R20") (pin "1") (pinfunction "1_1") (pintype "passive"))
      (node (ref "R21") (pin "2") (pinfunction "2_2") (pintype "passive"))
      (node (ref "U3") (pin "2") (pinfunction "REF_2") (pintype "input"))
    )
    (net (code "41") (name "Net-(U4-BOOT)") (class "Default")
      (node (ref "R22") (pin "2") (pinfunction "2_2") (pintype "passive"))
      (node (ref "U4") (pin "6") (pinfunction "BOOT_6") (pintype "power_in"))
    )
    (net (code "42") (name "Net-(U4-EN)") (class "Default")
      (node (ref "R24") (pin "1") (pinfunction "1_1") (pintype "passive"))
      (node (ref "R28") (pin "2") (pinfunction "2_2") (pintype "passive"))
      (node (ref "U4") (pin "5") (pinfunction "EN_5") (pintype "input"))
    )
    (net (code "43") (name "Net-(U4-FB)") (class "Default")
      (node (ref "C36") (pin "1") (pinfunction "1_1") (pintype "passive"))
      (node (ref "R26") (pin "1") (pinfunction "1_1") (pintype "passive"))
      (node (ref "R30") (pin "2") (pinfunction "2_2") (pintype "passive"))
      (node (ref "U4") (pin "4") (pinfunction "FB_4") (pintype "input"))
    )
    (net (code "44") (name "Net-(U4-SW)") (class "Default")
      (node (ref "C21") (pin "2") (pinfunction "2_2") (pintype "passive"))
      (node (ref "L2") (pin "1") (pinfunction "1_1") (pintype "passive"))
      (node (ref "U4") (pin "2") (pinfunction "SW_2") (pintype "power_in"))
    )
    (net (code "45") (name "Net-(U5-BOOT)") (class "Default")
      (node (ref "R23") (pin "2") (pinfunction "2_2") (pintype "passive"))
      (node (ref "U5") (pin "6") (pinfunction "BOOT_6") (pintype "power_in"))
    )
    (net (code "46") (name "Net-(U5-EN)") (class "Default")
      (node (ref "R25") (pin "1") (pinfunction "1_1") (pintype "passive"))
      (node (ref "R29") (pin "2") (pinfunction "2_2") (pintype "passive"))
      (node (ref "U5") (pin "5") (pinfunction "EN_5") (pintype "input"))
    )
    (net (code "47") (name "Net-(U5-FB)") (class "Default")
      (node (ref "C35") (pin "1") (pinfunction "1_1") (pintype "passive"))
      (node (ref "R27") (pin "1") (pinfunction "1_1") (pintype "passive"))
      (node (ref "R31") (pin "2") (pinfunction "2_2") (pintype "passive"))
      (node (ref "U5") (pin "4") (pinfunction "FB_4") (pintype "input"))
    )
    (net (code "48") (name "Net-(U5-SW)") (class "Default")
      (node (ref "C22") (pin "2") (pinfunction "2_2") (pintype "passive"))
      (node (ref "L3") (pin "1") (pinfunction "1_1") (pintype "passive"))
      (node (ref "U5") (pin "2") (pinfunction "SW_2") (pintype "power_in"))
    )
    (net (code "49") (name "VCC_AUX") (class "Default")
      (node (ref "C15") (pin "1") (pinfunction "1_1") (pintype "passive"))
      (node (ref "C16") (pin "2") (pinfunction "2_2") (pintype "passive"))
      (node (ref "C17") (pin "1") (pinfunction "1_1") (pintype "passive"))
      (node (ref "D8") (pin "2") (pinfunction "K_2") (pintype "passive"))
      (node (ref "D9") (pin "2") (pinfunction "K_2") (pintype "passive"))
      (node (ref "R16") (pin "2") (pinfunction "2_2") (pintype "passive"))
      (node (ref "U1") (pin "1") (pinfunction "VDD_1") (pintype "power_in"))
    )
    (net (code "50") (name "unconnected-(P3-Pad5)") (class "Default")
      (node (ref "P3") (pin "5") (pinfunction "5_5") (pintype "passive+no_connect"))
    )
    (net (code "51") (name "unconnected-(P3-Pad6)") (class "Default")
      (node (ref "P3") (pin "6") (pinfunction "6_6") (pintype "passive+no_connect"))
    )
    (net (code "52") (name "unconnected-(P3-Pad7)") (class "Default")
      (node (ref "P3") (pin "7") (pinfunction "7_7") (pintype "passive+no_connect"))
    )
    (net (code "53") (name "unconnected-(P3-Pad8)") (class "Default")
      (node (ref "P3") (pin "8") (pinfunction "8_8") (pintype "passive+no_connect"))
    )
    (net (code "54") (name "unconnected-(T1-Pad3)") (class "Default")
      (node (ref "T1") (pin "3") (pintype "passive"))
    )
    (net (code "55") (name "unconnected-(T1-Pad8)") (class "Default")
      (node (ref "T1") (pin "8") (pintype "passive"))
    )
    (net (code "56") (name "unconnected-(U1-NC-Pad7)") (class "Default")
      (node (ref "U1") (pin "7") (pinfunction "NC_7") (pintype "passive"))
    )
  )
)
